# Temperature_sensor_-_TC1046VNBTR.net
KiCad netlist of a schematic drawn in Altium Designer
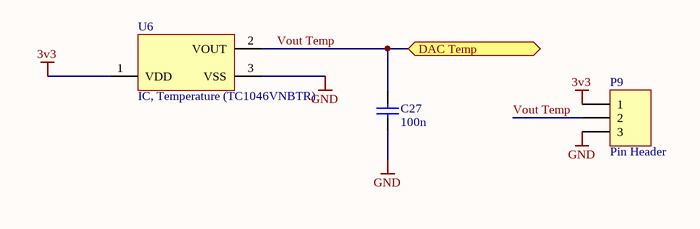
[diagram p0: Temperature sensor - TC1046VNBTR.SchDoc]

(export (version "E")
  (design (tool "Eeschema 10.0.6"))
  (components
    (comp (ref "C27")
      (value "100n")
      (footprint "C0805")
      (fields (field (name "TOLERANCE") "0.1") (field (name "AUTHOR") "Willy Pietersz"))
      (libsource (lib "OurDb") (part "cap_NonPolar"))
    )
    (comp (ref "P9")
      (value "Pin Header")
      (footprint "PH1x3_2.54")
      (description "Con1x3")
      (fields (field (name "PART NUMBER") "PH1x3") (field (name "AUTHOR") "Willy Pietersz"))
      (libsource (lib "OurDb") (part "Con1x3"))
    )
    (comp (ref "U6")
      (value "IC, Temperature (TC1046VNBTR)")
      (footprint "SOT-23-NB3_M")
      (description "High Precision Temperature-to-Voltage Converter, 3-Pin SOT-23, Extended Temperature, Tape and Reel")
      (fields (field (name "PUBLISHER") "Altium Limited"))
      (libsource (lib "AltiumDatabaseSelection") (part "TC1046VNBTR"))
    )
  )
  (nets
    (net (code "1") (name "/Vout Temp") (class "Default")
      (node (ref "C27") (pin "2") (pinfunction "2_2") (pintype "passive"))
      (node (ref "P9") (pin "2") (pinfunction "2_2") (pintype "passive"))
      (node (ref "U6") (pin "2") (pinfunction "VOUT_2") (pintype "power_in"))
    )
    (net (code "2") (name "3v3") (class "Default")
      (node (ref "P9") (pin "1") (pinfunction "1_1") (pintype "passive"))
      (node (ref "U6") (pin "1") (pinfunction "VDD_1") (pintype "power_in"))
    )
    (net (code "3") (name "GND") (class "Default")
      (node (ref "C27") (pin "1") (pinfunction "1_1") (pintype "passive"))
      (node (ref "P9") (pin "3") (pinfunction "3_3") (pintype "passive"))
      (node (ref "U6") (pin "3") (pinfunction "VSS_3") (pintype "power_in"))
    )
  )
)
